# Page_3.net
KiCad netlist of a schematic drawn in Altium Designer
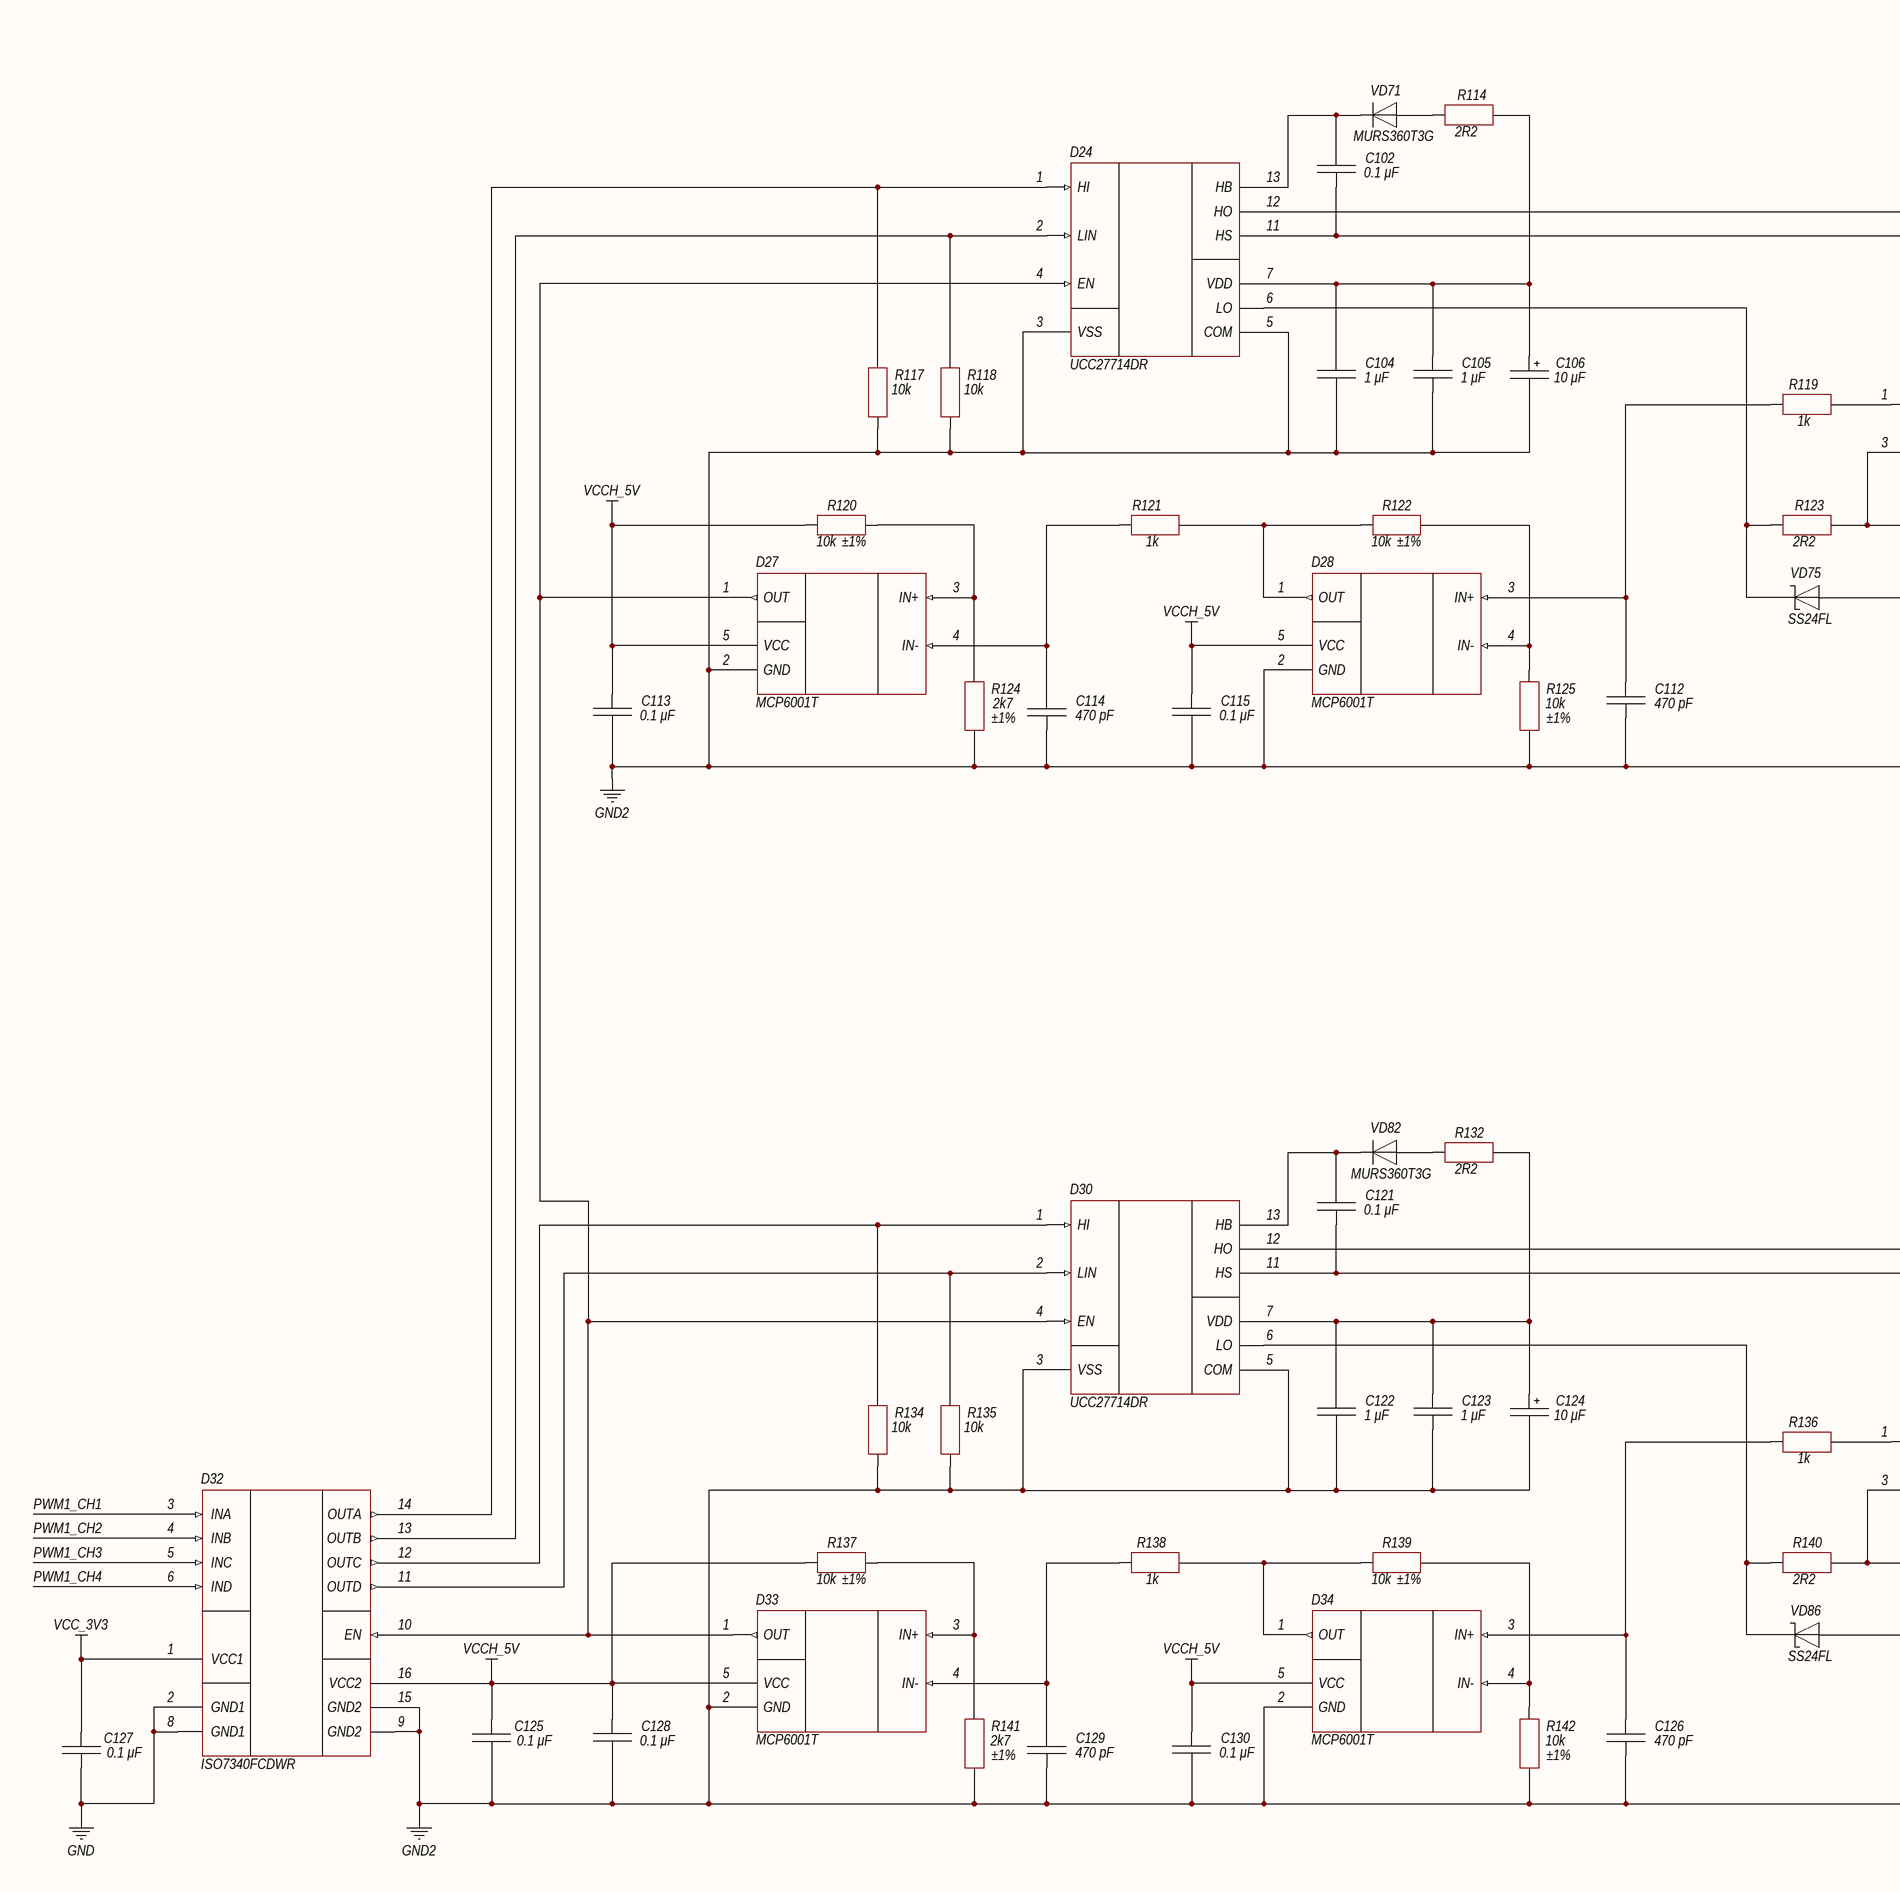
[diagram p0: Page 3.SchDoc, left]
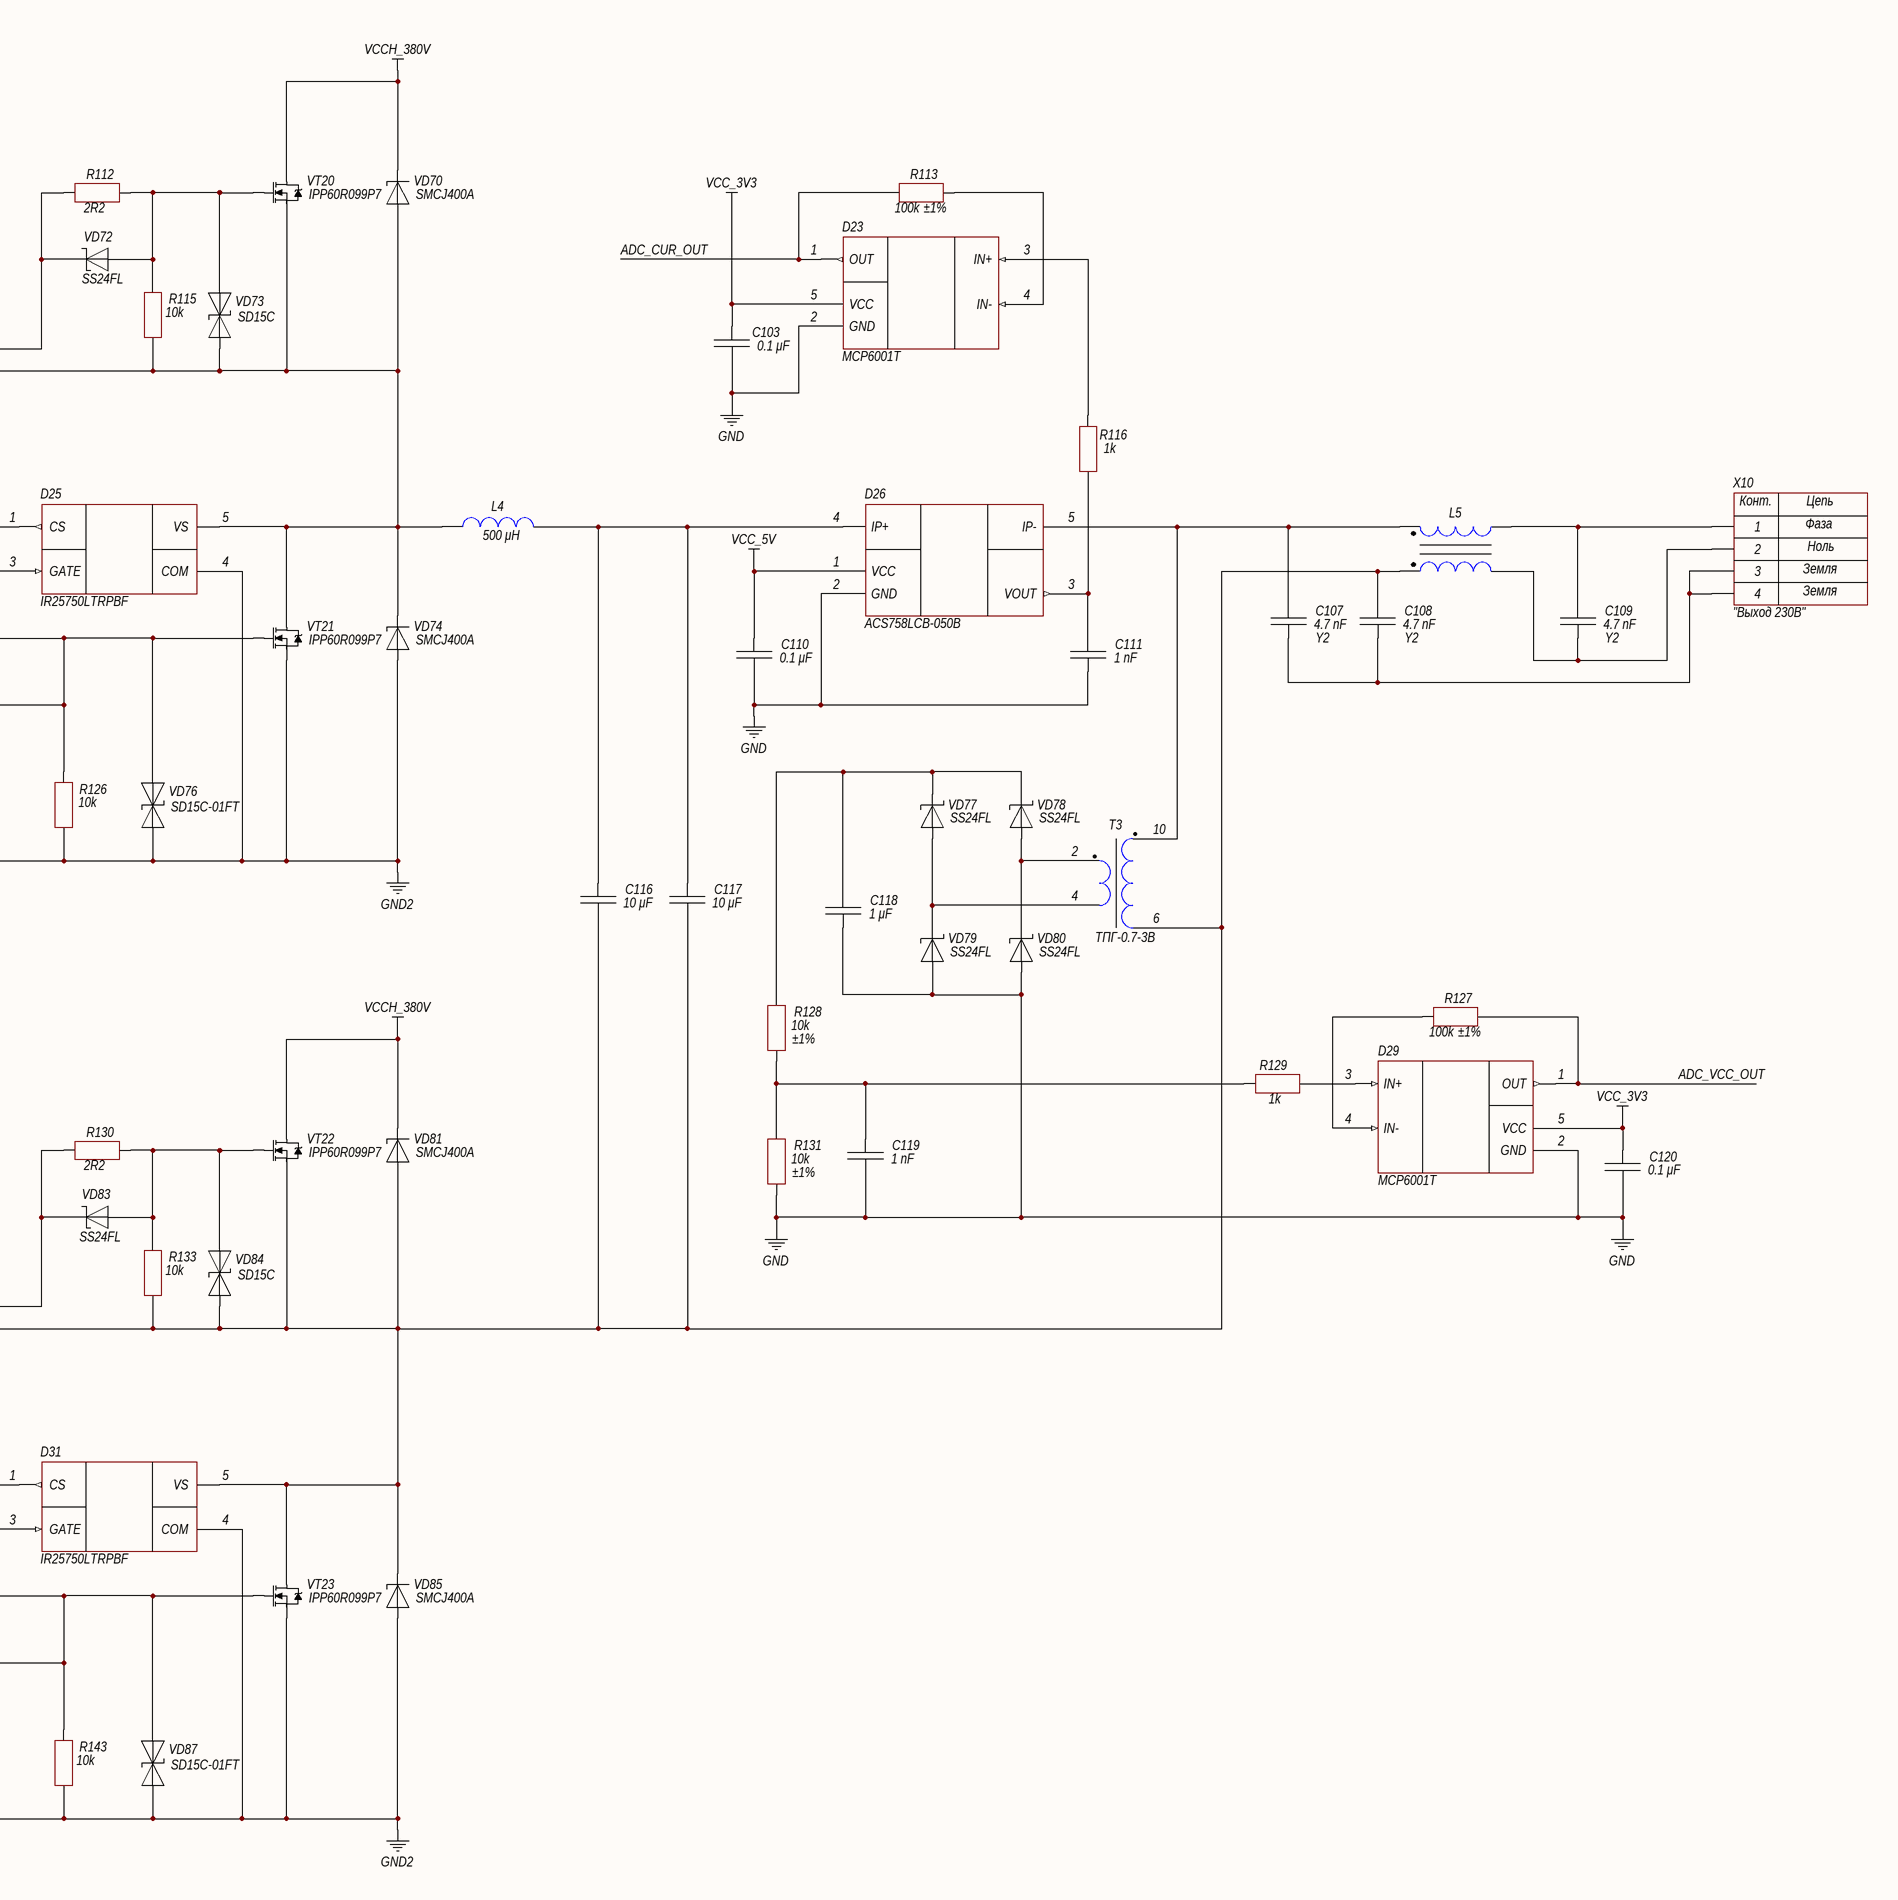
[diagram p1: Page 3.SchDoc, right]

(export (version "E")
  (design (tool "Eeschema 10.0.6"))
  (components
    (comp (ref "C102")
      (value "0.1 μF")
      (footprint "CH0805C")
      (fields (field (name "MANUFACTURER") "Yageo"))
      (libsource (lib "Discrete") (part "Capacitor"))
    )
    (comp (ref "C103")
      (value "0.1 μF")
      (footprint "CH0805C")
      (fields (field (name "MANUFACTURER") "Yageo"))
      (libsource (lib "Discrete") (part "Capacitor"))
    )
    (comp (ref "C104")
      (value "1 μF")
      (footprint "CH0805C")
      (fields (field (name "MANUFACTURER") "Yageo"))
      (libsource (lib "Discrete") (part "Capacitor"))
    )
    (comp (ref "C105")
      (value "1 μF")
      (footprint "CH0805C")
      (fields (field (name "MANUFACTURER") "Yageo"))
      (libsource (lib "Discrete") (part "Capacitor"))
    )
    (comp (ref "C106")
      (value "10 μF")
      (footprint "TANTAL_C")
      (fields (field (name "MANUFACTURER") "Vishay Sprague"))
      (libsource (lib "Discrete") (part "TantalCap"))
    )
    (comp (ref "C107")
      (value "4.7 nF")
      (footprint "CAP: B32021")
      (fields (field (name "MANUFACTURER") "EPCOS (TDK)") (field (name "COMPONENTKIND") "Y2"))
      (libsource (lib "Discrete") (part "Capacitor"))
    )
    (comp (ref "C108")
      (value "4.7 nF")
      (footprint "CAP: B32021")
      (fields (field (name "MANUFACTURER") "EPCOS (TDK)") (field (name "COMPONENTKIND") "Y2"))
      (libsource (lib "Discrete") (part "Capacitor"))
    )
    (comp (ref "C109")
      (value "4.7 nF")
      (footprint "CAP: B32021")
      (fields (field (name "MANUFACTURER") "EPCOS (TDK)") (field (name "COMPONENTKIND") "Y2"))
      (libsource (lib "Discrete") (part "Capacitor"))
    )
    (comp (ref "C110")
      (value "0.1 μF")
      (footprint "CH0805C")
      (fields (field (name "MANUFACTURER") "Yageo"))
      (libsource (lib "Discrete") (part "Capacitor"))
    )
    (comp (ref "C111")
      (value "1 nF")
      (footprint "CH0805C")
      (fields (field (name "MANUFACTURER") "Yageo"))
      (libsource (lib "Discrete") (part "Capacitor"))
    )
    (comp (ref "C112")
      (value "470 pF")
      (footprint "CH0805C")
      (fields (field (name "MANUFACTURER") "Yageo"))
      (libsource (lib "Discrete") (part "Capacitor"))
    )
    (comp (ref "C113")
      (value "0.1 μF")
      (footprint "CH0805C")
      (fields (field (name "MANUFACTURER") "Yageo"))
      (libsource (lib "Discrete") (part "Capacitor"))
    )
    (comp (ref "C114")
      (value "470 pF")
      (footprint "CH0805C")
      (fields (field (name "MANUFACTURER") "Yageo"))
      (libsource (lib "Discrete") (part "Capacitor"))
    )
    (comp (ref "C115")
      (value "0.1 μF")
      (footprint "CH0805C")
      (fields (field (name "MANUFACTURER") "Yageo"))
      (libsource (lib "Discrete") (part "Capacitor"))
    )
    (comp (ref "C116")
      (value "10 μF")
      (footprint "CAP: B32676")
      (fields (field (name "MANUFACTURER") "Epcos"))
      (libsource (lib "Discrete") (part "Capacitor"))
    )
    (comp (ref "C117")
      (value "10 μF")
      (footprint "CAP: B32676")
      (fields (field (name "MANUFACTURER") "Epcos"))
      (libsource (lib "Discrete") (part "Capacitor"))
    )
    (comp (ref "C118")
      (value "1 μF")
      (footprint "CH0805C")
      (fields (field (name "MANUFACTURER") "Yageo"))
      (libsource (lib "Discrete") (part "Capacitor"))
    )
    (comp (ref "C119")
      (value "1 nF")
      (footprint "CH0805C")
      (fields (field (name "MANUFACTURER") "Yageo"))
      (libsource (lib "Discrete") (part "Capacitor"))
    )
    (comp (ref "C120")
      (value "0.1 μF")
      (footprint "CH0805C")
      (fields (field (name "MANUFACTURER") "Yageo"))
      (libsource (lib "Discrete") (part "Capacitor"))
    )
    (comp (ref "C121")
      (value "0.1 μF")
      (footprint "CH0805C")
      (fields (field (name "MANUFACTURER") "Yageo"))
      (libsource (lib "Discrete") (part "Capacitor"))
    )
    (comp (ref "C122")
      (value "1 μF")
      (footprint "CH0805C")
      (fields (field (name "MANUFACTURER") "Yageo"))
      (libsource (lib "Discrete") (part "Capacitor"))
    )
    (comp (ref "C123")
      (value "1 μF")
      (footprint "CH0805C")
      (fields (field (name "MANUFACTURER") "Yageo"))
      (libsource (lib "Discrete") (part "Capacitor"))
    )
    (comp (ref "C124")
      (value "10 μF")
      (footprint "TANTAL_C")
      (fields (field (name "MANUFACTURER") "Vishay Sprague"))
      (libsource (lib "Discrete") (part "TantalCap"))
    )
    (comp (ref "C125")
      (value "0.1 μF")
      (footprint "CH0805C")
      (fields (field (name "MANUFACTURER") "Yageo"))
      (libsource (lib "Discrete") (part "Capacitor"))
    )
    (comp (ref "C126")
      (value "470 pF")
      (footprint "CH0805C")
      (fields (field (name "MANUFACTURER") "Yageo"))
      (libsource (lib "Discrete") (part "Capacitor"))
    )
    (comp (ref "C127")
      (value "0.1 μF")
      (footprint "CH0805C")
      (fields (field (name "MANUFACTURER") "Yageo"))
      (libsource (lib "Discrete") (part "Capacitor"))
    )
    (comp (ref "C128")
      (value "0.1 μF")
      (footprint "CH0805C")
      (fields (field (name "MANUFACTURER") "Yageo"))
      (libsource (lib "Discrete") (part "Capacitor"))
    )
    (comp (ref "C129")
      (value "470 pF")
      (footprint "CH0805C")
      (fields (field (name "MANUFACTURER") "Yageo"))
      (libsource (lib "Discrete") (part "Capacitor"))
    )
    (comp (ref "C130")
      (value "0.1 μF")
      (footprint "CH0805C")
      (fields (field (name "MANUFACTURER") "Yageo"))
      (libsource (lib "Discrete") (part "Capacitor"))
    )
    (comp (ref "D23")
      (value "MCP6001T")
      (footprint "SOT23-5")
      (description "OP amplifier")
      (fields (field (name "MANUFACTURER") "Microchip Technology"))
      (libsource (lib "") (part "MCP6001T_1"))
    )
    (comp (ref "D24")
      (value "UCC27714DR")
      (footprint "14-SOIC")
      (description "Half-bridge driver")
      (fields (field (name "MANUFACTURER") "Texas Instruments"))
      (libsource (lib "Power Supplies") (part "UCC27714DR"))
    )
    (comp (ref "D25")
      (value "IR25750LTRPBF")
      (footprint "SOT23-5")
      (description "Sensor")
      (fields (field (name "MANUFACTURER") "Infineon Technologies"))
      (libsource (lib "Power Supplies") (part "IR25750LTRPBF"))
    )
    (comp (ref "D26")
      (value "ACS758LCB-050B")
      (footprint "IC: ACS770")
      (description "Sensor")
      (fields (field (name "MANUFACTURER") "Allegro MicroSystems, LLC"))
      (libsource (lib "Power Supplies") (part "ACS770LCB"))
    )
    (comp (ref "D27")
      (value "MCP6001T")
      (footprint "SOT23-5")
      (description "OP amplifier")
      (fields (field (name "MANUFACTURER") "Microchip Technology"))
      (libsource (lib "") (part "MCP6001T_1"))
    )
    (comp (ref "D28")
      (value "MCP6001T")
      (footprint "SOT23-5")
      (description "OP amplifier")
      (fields (field (name "MANUFACTURER") "Microchip Technology"))
      (libsource (lib "") (part "MCP6001T_1"))
    )
    (comp (ref "D29")
      (value "MCP6001T")
      (footprint "SOT23-5")
      (description "OP amplifier")
      (fields (field (name "MANUFACTURER") "Microchip Technology"))
      (libsource (lib "Analog") (part "MCP6001T"))
    )
    (comp (ref "D30")
      (value "UCC27714DR")
      (footprint "14-SOIC")
      (description "Half-bridge driver")
      (fields (field (name "MANUFACTURER") "Texas Instruments"))
      (libsource (lib "Power Supplies") (part "UCC27714DR"))
    )
    (comp (ref "D31")
      (value "IR25750LTRPBF")
      (footprint "SOT23-5")
      (description "Sensor")
      (fields (field (name "MANUFACTURER") "Infineon Technologies"))
      (libsource (lib "Power Supplies") (part "IR25750LTRPBF"))
    )
    (comp (ref "D32")
      (value "ISO7340FCDWR")
      (footprint "16-SOIC (W)")
      (description "Isolator")
      (fields (field (name "MANUFACTURER") "Texas Instruments"))
      (libsource (lib "Analog") (part "ISO7340FCDWR"))
    )
    (comp (ref "D33")
      (value "MCP6001T")
      (footprint "SOT23-5")
      (description "OP amplifier")
      (fields (field (name "MANUFACTURER") "Microchip Technology"))
      (libsource (lib "") (part "MCP6001T_1"))
    )
    (comp (ref "D34")
      (value "MCP6001T")
      (footprint "SOT23-5")
      (description "OP amplifier")
      (fields (field (name "MANUFACTURER") "Microchip Technology"))
      (libsource (lib "") (part "MCP6001T_1"))
    )
    (comp (ref "L4")
      (value "500 μH")
      (footprint "IND: R46")
      (fields (field (name "MANUFACTURER") "Magnetics"))
      (libsource (lib "Transformers") (part "Inductor ring"))
    )
    (comp (ref "L5")
      (value "0077071A7")
      (footprint "IND: R32")
      (fields (field (name "MANUFACTURER") "Magnetics"))
      (libsource (lib "Transformers") (part "EMI filter"))
    )
    (comp (ref "R112")
      (value "2R2")
      (footprint "CH0805R")
      (fields (field (name "MANUFACTURER") "Yageo"))
      (libsource (lib "") (part "Resistor_1"))
    )
    (comp (ref "R113")
      (value "100k")
      (footprint "CH0805R")
      (fields (field (name "MANUFACTURER") "Yageo") (field (name "COMPONENTKIND") "±1%"))
      (libsource (lib "") (part "Resistor_3"))
    )
    (comp (ref "R114")
      (value "2R2")
      (footprint "CH0805R")
      (fields (field (name "MANUFACTURER") "Yageo"))
      (libsource (lib "") (part "Resistor_1"))
    )
    (comp (ref "R115")
      (value "10k")
      (footprint "CH0805R")
      (fields (field (name "MANUFACTURER") "Yageo"))
      (libsource (lib "Discrete") (part "Resistor"))
    )
    (comp (ref "R116")
      (value "1k")
      (footprint "CH0805R")
      (fields (field (name "MANUFACTURER") "Yageo"))
      (libsource (lib "") (part "Resistor_1"))
    )
    (comp (ref "R117")
      (value "10k")
      (footprint "CH0805R")
      (fields (field (name "MANUFACTURER") "Yageo"))
      (libsource (lib "Discrete") (part "Resistor"))
    )
    (comp (ref "R118")
      (value "10k")
      (footprint "CH0805R")
      (fields (field (name "MANUFACTURER") "Yageo"))
      (libsource (lib "Discrete") (part "Resistor"))
    )
    (comp (ref "R119")
      (value "1k")
      (footprint "CH0805R")
      (fields (field (name "MANUFACTURER") "Yageo"))
      (libsource (lib "Discrete") (part "Resistor"))
    )
    (comp (ref "R120")
      (value "10k")
      (footprint "CH0805R")
      (fields (field (name "MANUFACTURER") "Yageo") (field (name "COMPONENTKIND") "±1%"))
      (libsource (lib "") (part "Resistor_1"))
    )
    (comp (ref "R121")
      (value "1k")
      (footprint "CH0805R")
      (fields (field (name "MANUFACTURER") "Yageo"))
      (libsource (lib "") (part "Resistor_2"))
    )
    (comp (ref "R122")
      (value "10k")
      (footprint "CH0805R")
      (fields (field (name "MANUFACTURER") "Yageo") (field (name "COMPONENTKIND") "±1%"))
      (libsource (lib "") (part "Resistor_3"))
    )
    (comp (ref "R123")
      (value "2R2")
      (footprint "CH0805R")
      (fields (field (name "MANUFACTURER") "Yageo"))
      (libsource (lib "") (part "Resistor_1"))
    )
    (comp (ref "R124")
      (value "2k7")
      (footprint "CH0805R")
      (fields (field (name "MANUFACTURER") "Yageo") (field (name "COMPONENTKIND") "±1%"))
      (libsource (lib "") (part "Resistor_2"))
    )
    (comp (ref "R125")
      (value "10k")
      (footprint "CH0805R")
      (fields (field (name "MANUFACTURER") "Yageo") (field (name "COMPONENTKIND") "±1%"))
      (libsource (lib "") (part "Resistor_2"))
    )
    (comp (ref "R126")
      (value "10k")
      (footprint "CH0805R")
      (fields (field (name "MANUFACTURER") "Yageo"))
      (libsource (lib "Discrete") (part "Resistor"))
    )
    (comp (ref "R127")
      (value "100k")
      (footprint "CH0805R")
      (fields (field (name "MANUFACTURER") "Yageo") (field (name "COMPONENTKIND") "±1%"))
      (libsource (lib "") (part "Resistor_3"))
    )
    (comp (ref "R128")
      (value "10k")
      (footprint "CH0805R")
      (fields (field (name "MANUFACTURER") "Yageo") (field (name "COMPONENTKIND") "±1%"))
      (libsource (lib "") (part "Resistor_2"))
    )
    (comp (ref "R129")
      (value "1k")
      (footprint "CH0805R")
      (fields (field (name "MANUFACTURER") "Yageo"))
      (libsource (lib "") (part "Resistor_2"))
    )
    (comp (ref "R130")
      (value "2R2")
      (footprint "CH0805R")
      (fields (field (name "MANUFACTURER") "Yageo"))
      (libsource (lib "") (part "Resistor_1"))
    )
    (comp (ref "R131")
      (value "10k")
      (footprint "CH0805R")
      (fields (field (name "MANUFACTURER") "Yageo") (field (name "COMPONENTKIND") "±1%"))
      (libsource (lib "") (part "Resistor_2"))
    )
    (comp (ref "R132")
      (value "2R2")
      (footprint "CH0805R")
      (fields (field (name "MANUFACTURER") "Yageo"))
      (libsource (lib "") (part "Resistor_1"))
    )
    (comp (ref "R133")
      (value "10k")
      (footprint "CH0805R")
      (fields (field (name "MANUFACTURER") "Yageo"))
      (libsource (lib "Discrete") (part "Resistor"))
    )
    (comp (ref "R134")
      (value "10k")
      (footprint "CH0805R")
      (fields (field (name "MANUFACTURER") "Yageo"))
      (libsource (lib "Discrete") (part "Resistor"))
    )
    (comp (ref "R135")
      (value "10k")
      (footprint "CH0805R")
      (fields (field (name "MANUFACTURER") "Yageo"))
      (libsource (lib "Discrete") (part "Resistor"))
    )
    (comp (ref "R136")
      (value "1k")
      (footprint "CH0805R")
      (fields (field (name "MANUFACTURER") "Yageo"))
      (libsource (lib "Discrete") (part "Resistor"))
    )
    (comp (ref "R137")
      (value "10k")
      (footprint "CH0805R")
      (fields (field (name "MANUFACTURER") "Yageo") (field (name "COMPONENTKIND") "±1%"))
      (libsource (lib "") (part "Resistor_1"))
    )
    (comp (ref "R138")
      (value "1k")
      (footprint "CH0805R")
      (fields (field (name "MANUFACTURER") "Yageo"))
      (libsource (lib "") (part "Resistor_2"))
    )
    (comp (ref "R139")
      (value "10k")
      (footprint "CH0805R")
      (fields (field (name "MANUFACTURER") "Yageo") (field (name "COMPONENTKIND") "±1%"))
      (libsource (lib "") (part "Resistor_3"))
    )
    (comp (ref "R140")
      (value "2R2")
      (footprint "CH0805R")
      (fields (field (name "MANUFACTURER") "Yageo"))
      (libsource (lib "") (part "Resistor_1"))
    )
    (comp (ref "R141")
      (value "2k7")
      (footprint "CH0805R")
      (fields (field (name "MANUFACTURER") "Yageo") (field (name "COMPONENTKIND") "±1%"))
      (libsource (lib "") (part "Resistor_2"))
    )
    (comp (ref "R142")
      (value "10k")
      (footprint "CH0805R")
      (fields (field (name "MANUFACTURER") "Yageo") (field (name "COMPONENTKIND") "±1%"))
      (libsource (lib "") (part "Resistor_2"))
    )
    (comp (ref "R143")
      (value "10k")
      (footprint "CH0805R")
      (fields (field (name "MANUFACTURER") "Yageo"))
      (libsource (lib "Discrete") (part "Resistor"))
    )
    (comp (ref "T3")
      (value "ТПГ-0.7-3В")
      (footprint "TRANS: ТПК-7")
      (description "Sensor")
      (fields (field (name "MANUFACTURER") "НПК «Комплекс»"))
      (libsource (lib "Transformers") (part "Sensor"))
    )
    (comp (ref "VD70")
      (value "SMCJ400A")
      (footprint "SMC")
      (fields (field (name "MANUFACTURER") "Littelfuse Inc."))
      (libsource (lib "Diods") (part "Diod Zener"))
    )
    (comp (ref "VD71")
      (value "MURS360T3G")
      (footprint "SMC")
      (fields (field (name "MANUFACTURER") "ON Semiconductor"))
      (libsource (lib "Diods") (part "Diod"))
    )
    (comp (ref "VD72")
      (value "SS24FL")
      (footprint "SOD123F")
      (fields (field (name "MANUFACTURER") "Fairchild/ON Semiconductor"))
      (libsource (lib "Diods") (part "Diod Schottky"))
    )
    (comp (ref "VD73")
      (value "SD15C")
      (footprint "SOD323")
      (fields (field (name "MANUFACTURER") "Littelfuse Inc."))
      (libsource (lib "Diods") (part "TVS-diod"))
    )
    (comp (ref "VD74")
      (value "SMCJ400A")
      (footprint "SMC")
      (fields (field (name "MANUFACTURER") "Littelfuse Inc."))
      (libsource (lib "Diods") (part "Diod Zener"))
    )
    (comp (ref "VD75")
      (value "SS24FL")
      (footprint "SOD123F")
      (fields (field (name "MANUFACTURER") "Fairchild/ON Semiconductor"))
      (libsource (lib "Diods") (part "Diod Schottky"))
    )
    (comp (ref "VD76")
      (value "SD15C-01FT")
      (footprint "SOD323")
      (fields (field (name "MANUFACTURER") "Littelfuse Inc."))
      (libsource (lib "Diods") (part "TVS-diod"))
    )
    (comp (ref "VD77")
      (value "SS24FL")
      (footprint "SOD123F")
      (fields (field (name "MANUFACTURER") "Fairchild/ON Semiconductor"))
      (libsource (lib "Diods") (part "Diod Schottky"))
    )
    (comp (ref "VD78")
      (value "SS24FL")
      (footprint "SOD123F")
      (fields (field (name "MANUFACTURER") "Fairchild/ON Semiconductor"))
      (libsource (lib "Diods") (part "Diod Schottky"))
    )
    (comp (ref "VD79")
      (value "SS24FL")
      (footprint "SOD123F")
      (fields (field (name "MANUFACTURER") "Fairchild/ON Semiconductor"))
      (libsource (lib "Diods") (part "Diod Schottky"))
    )
    (comp (ref "VD80")
      (value "SS24FL")
      (footprint "SOD123F")
      (fields (field (name "MANUFACTURER") "Fairchild/ON Semiconductor"))
      (libsource (lib "Diods") (part "Diod Schottky"))
    )
    (comp (ref "VD81")
      (value "SMCJ400A")
      (footprint "SMC")
      (fields (field (name "MANUFACTURER") "Littelfuse Inc."))
      (libsource (lib "Diods") (part "Diod Zener"))
    )
    (comp (ref "VD82")
      (value "MURS360T3G")
      (footprint "SMC")
      (fields (field (name "MANUFACTURER") "ON Semiconductor"))
      (libsource (lib "Diods") (part "Diod"))
    )
    (comp (ref "VD83")
      (value "SS24FL")
      (footprint "SOD123F")
      (fields (field (name "MANUFACTURER") "Fairchild/ON Semiconductor"))
      (libsource (lib "Diods") (part "Diod Schottky"))
    )
    (comp (ref "VD84")
      (value "SD15C")
      (footprint "SOD323")
      (fields (field (name "MANUFACTURER") "Littelfuse Inc."))
      (libsource (lib "Diods") (part "TVS-diod"))
    )
    (comp (ref "VD85")
      (value "SMCJ400A")
      (footprint "SMC")
      (fields (field (name "MANUFACTURER") "Littelfuse Inc."))
      (libsource (lib "Diods") (part "Diod Zener"))
    )
    (comp (ref "VD86")
      (value "SS24FL")
      (footprint "SOD123F")
      (fields (field (name "MANUFACTURER") "Fairchild/ON Semiconductor"))
      (libsource (lib "Diods") (part "Diod Schottky"))
    )
    (comp (ref "VD87")
      (value "SD15C-01FT")
      (footprint "SOD323")
      (fields (field (name "MANUFACTURER") "Littelfuse Inc."))
      (libsource (lib "Diods") (part "TVS-diod"))
    )
    (comp (ref "VT20")
      (value "IPP60R099P7")
      (footprint "TO220_123")
      (description "Mosfet")
      (fields (field (name "MANUFACTURER") "Infineon Technologies"))
      (libsource (lib "Transistor") (part "N-chanel"))
    )
    (comp (ref "VT21")
      (value "IPP60R099P7")
      (footprint "TO220_123")
      (description "Mosfet")
      (fields (field (name "MANUFACTURER") "Infineon Technologies"))
      (libsource (lib "Transistor") (part "N-chanel"))
    )
    (comp (ref "VT22")
      (value "IPP60R099P7")
      (footprint "TO220_123")
      (description "Mosfet")
      (fields (field (name "MANUFACTURER") "Infineon Technologies"))
      (libsource (lib "Transistor") (part "N-chanel"))
    )
    (comp (ref "VT23")
      (value "IPP60R099P7")
      (footprint "TO220_123")
      (description "Mosfet")
      (fields (field (name "MANUFACTURER") "Infineon Technologies"))
      (libsource (lib "Transistor") (part "N-chanel"))
    )
    (comp (ref "X10")
      (value "\"Выход 230В\"")
      (footprint "CON: X977B04")
      (fields (field (name "MANUFACTURER") "Ningbo Xinya M&E"))
      (libsource (lib "Connectors") (part "4-Connector"))
    )
  )
  (nets
    (net (code "1") (name "/ADC_CUR_OUT") (class "Default")
      (node (ref "D23") (pin "1") (pinfunction "OUT_1") (pintype "output"))
      (node (ref "R113") (pin "1") (pinfunction "1_1") (pintype "passive"))
    )
    (net (code "2") (name "/ADC_VCC_OUT") (class "Default")
      (node (ref "D29") (pin "1") (pinfunction "OUT_1") (pintype "output"))
      (node (ref "R127") (pin "2") (pinfunction "2_2") (pintype "passive"))
    )
    (net (code "3") (name "/PWM1_CH1") (class "Default")
      (node (ref "D32") (pin "3") (pinfunction "INA_3") (pintype "input"))
    )
    (net (code "4") (name "/PWM1_CH2") (class "Default")
      (node (ref "D32") (pin "4") (pinfunction "INB_4") (pintype "input"))
    )
    (net (code "5") (name "/PWM1_CH3") (class "Default")
      (node (ref "D32") (pin "5") (pinfunction "INC_5") (pintype "input"))
    )
    (net (code "6") (name "/PWM1_CH4") (class "Default")
      (node (ref "D32") (pin "6") (pinfunction "IND_6") (pintype "input"))
    )
    (net (code "7") (name "GND") (class "Default")
      (node (ref "C103") (pin "1") (pinfunction "1_1") (pintype "power_in"))
      (node (ref "C110") (pin "1") (pinfunction "1_1") (pintype "power_in"))
      (node (ref "C111") (pin "1") (pinfunction "1_1") (pintype "power_in"))
      (node (ref "C118") (pin "1") (pinfunction "1_1") (pintype "power_in"))
      (node (ref "C119") (pin "1") (pinfunction "1_1") (pintype "power_in"))
      (node (ref "C120") (pin "1") (pinfunction "1_1") (pintype "power_in"))
      (node (ref "C127") (pin "1") (pinfunction "1_1") (pintype "power_in"))
      (node (ref "D23") (pin "2") (pinfunction "GND_2") (pintype "power_in"))
      (node (ref "D26") (pin "2") (pinfunction "GND_2") (pintype "passive"))
      (node (ref "D29") (pin "2") (pinfunction "GND_2") (pintype "power_in"))
      (node (ref "D32") (pin "2") (pinfunction "GND1_2") (pintype "power_in"))
      (node (ref "D32") (pin "8") (pinfunction "GND1_8") (pintype "power_in"))
      (node (ref "R131") (pin "2") (pinfunction "2_2") (pintype "passive"))
      (node (ref "VD79") (pin "1") (pinfunction "1_1") (pintype "passive"))
      (node (ref "VD80") (pin "1") (pinfunction "1_1") (pintype "passive"))
    )
    (net (code "8") (name "GND2") (class "Default")
      (node (ref "C104") (pin "1") (pinfunction "1_1") (pintype "power_in"))
      (node (ref "C105") (pin "1") (pinfunction "1_1") (pintype "power_in"))
      (node (ref "C106") (pin "2") (pinfunction "2_2") (pintype "power_in"))
      (node (ref "C112") (pin "2") (pinfunction "2_2") (pintype "power_in"))
      (node (ref "C113") (pin "1") (pinfunction "1_1") (pintype "power_in"))
      (node (ref "C114") (pin "2") (pinfunction "2_2") (pintype "power_in"))
      (node (ref "C115") (pin "1") (pinfunction "1_1") (pintype "power_in"))
      (node (ref "C122") (pin "1") (pinfunction "1_1") (pintype "power_in"))
      (node (ref "C123") (pin "1") (pinfunction "1_1") (pintype "power_in"))
      (node (ref "C124") (pin "2") (pinfunction "2_2") (pintype "power_in"))
      (node (ref "C125") (pin "1") (pinfunction "1_1") (pintype "power_in"))
      (node (ref "C126") (pin "2") (pinfunction "2_2") (pintype "power_in"))
      (node (ref "C128") (pin "1") (pinfunction "1_1") (pintype "power_in"))
      (node (ref "C129") (pin "2") (pinfunction "2_2") (pintype "power_in"))
      (node (ref "C130") (pin "1") (pinfunction "1_1") (pintype "power_in"))
      (node (ref "D24") (pin "3") (pinfunction "VSS_3") (pintype "passive"))
      (node (ref "D24") (pin "5") (pinfunction "COM_5") (pintype "passive"))
      (node (ref "D25") (pin "4") (pinfunction "COM_4") (pintype "power_in"))
      (node (ref "D27") (pin "2") (pinfunction "GND_2") (pintype "power_in"))
      (node (ref "D28") (pin "2") (pinfunction "GND_2") (pintype "power_in"))
      (node (ref "D30") (pin "3") (pinfunction "VSS_3") (pintype "passive"))
      (node (ref "D30") (pin "5") (pinfunction "COM_5") (pintype "passive"))
      (node (ref "D31") (pin "4") (pinfunction "COM_4") (pintype "power_in"))
      (node (ref "D32") (pin "15") (pinfunction "GND2_15") (pintype "power_in"))
      (node (ref "D32") (pin "9") (pinfunction "GND2_9") (pintype "power_in"))
      (node (ref "D33") (pin "2") (pinfunction "GND_2") (pintype "power_in"))
      (node (ref "D34") (pin "2") (pinfunction "GND_2") (pintype "power_in"))
      (node (ref "R117") (pin "1") (pinfunction "1_1") (pintype "passive"))
      (node (ref "R118") (pin "1") (pinfunction "1_1") (pintype "passive"))
      (node (ref "R124") (pin "2") (pinfunction "2_2") (pintype "passive"))
      (node (ref "R125") (pin "2") (pinfunction "2_2") (pintype "passive"))
      (node (ref "R126") (pin "1") (pinfunction "1_1") (pintype "passive"))
      (node (ref "R134") (pin "1") (pinfunction "1_1") (pintype "passive"))
      (node (ref "R135") (pin "1") (pinfunction "1_1") (pintype "passive"))
      (node (ref "R141") (pin "2") (pinfunction "2_2") (pintype "passive"))
      (node (ref "R142") (pin "2") (pinfunction "2_2") (pintype "passive"))
      (node (ref "R143") (pin "1") (pinfunction "1_1") (pintype "passive"))
      (node (ref "VD74") (pin "1") (pinfunction "A_1") (pintype "passive"))
      (node (ref "VD76") (pin "1") (pinfunction "A_1") (pintype "passive"))
      (node (ref "VD85") (pin "1") (pinfunction "A_1") (pintype "passive"))
      (node (ref "VD87") (pin "1") (pinfunction "A_1") (pintype "passive"))
      (node (ref "VT21") (pin "3") (pinfunction "S_3") (pintype "passive"))
      (node (ref "VT23") (pin "3") (pinfunction "S_3") (pintype "passive"))
    )
    (net (code "9") (name "Net-(C107-Pad1)") (class "Default")
      (node (ref "C107") (pin "1") (pinfunction "1_1") (pintype "power_in"))
      (node (ref "C108") (pin "1") (pinfunction "1_1") (pintype "power_in"))
      (node (ref "X10") (pin "3") (pinfunction "3_3") (pintype "power_in"))
      (node (ref "X10") (pin "4") (pinfunction "4_4") (pintype "power_in"))
    )
    (net (code "10") (name "Net-(C109-Pad1)") (class "Default")
      (node (ref "C109") (pin "1") (pinfunction "1_1") (pintype "power_in"))
      (node (ref "L5") (pin "4") (pinfunction "4_4") (pintype "passive"))
      (node (ref "X10") (pin "2") (pinfunction "2_2") (pintype "passive"))
    )
    (net (code "11") (name "Net-(C109-Pad2)") (class "Default")
      (node (ref "C109") (pin "2") (pinfunction "2_2") (pintype "power_in"))
      (node (ref "L5") (pin "2") (pinfunction "2_2") (pintype "passive"))
      (node (ref "X10") (pin "1") (pinfunction "1_1") (pintype "passive"))
    )
    (net (code "12") (name "Net-(C118-Pad2)") (class "Default")
      (node (ref "C118") (pin "2") (pinfunction "2_2") (pintype "power_in"))
      (node (ref "R128") (pin "1") (pinfunction "1_1") (pintype "passive"))
      (node (ref "VD77") (pin "2") (pinfunction "2_2") (pintype "passive"))
      (node (ref "VD78") (pin "2") (pinfunction "2_2") (pintype "passive"))
    )
    (net (code "13") (name "Net-(C119-Pad2)") (class "Default")
      (node (ref "C119") (pin "2") (pinfunction "2_2") (pintype "power_in"))
      (node (ref "R128") (pin "2") (pinfunction "2_2") (pintype "passive"))
      (node (ref "R129") (pin "2") (pinfunction "2_2") (pintype "passive"))
      (node (ref "R131") (pin "1") (pinfunction "1_1") (pintype "passive"))
    )
    (net (code "14") (name "Net-(D23-IN+)") (class "Default")
      (node (ref "D23") (pin "3") (pinfunction "IN+_3") (pintype "input"))
      (node (ref "R116") (pin "1") (pinfunction "1_1") (pintype "passive"))
    )
    (net (code "15") (name "Net-(D23-IN-)") (class "Default")
      (node (ref "D23") (pin "4") (pinfunction "IN-_4") (pintype "input"))
      (node (ref "R113") (pin "2") (pinfunction "2_2") (pintype "passive"))
    )
    (net (code "16") (name "Net-(D24-EN)") (class "Default")
      (node (ref "D24") (pin "4") (pinfunction "EN_4") (pintype "input"))
      (node (ref "D27") (pin "1") (pinfunction "OUT_1") (pintype "output"))
      (node (ref "D30") (pin "4") (pinfunction "EN_4") (pintype "input"))
      (node (ref "D32") (pin "10") (pinfunction "EN_10") (pintype "input"))
      (node (ref "D33") (pin "1") (pinfunction "OUT_1") (pintype "output"))
    )
    (net (code "17") (name "Net-(D24-HB)") (class "Default")
      (node (ref "C102") (pin "2") (pinfunction "2_2") (pintype "power_in"))
      (node (ref "D24") (pin "13") (pinfunction "HB_13") (pintype "passive"))
      (node (ref "VD71") (pin "2") (pinfunction "2_2") (pintype "passive"))
    )
    (net (code "18") (name "Net-(D24-HI)") (class "Default")
      (node (ref "D24") (pin "1") (pinfunction "HI_1") (pintype "input"))
      (node (ref "D32") (pin "14") (pinfunction "OUTA_14") (pintype "output"))
      (node (ref "R117") (pin "2") (pinfunction "2_2") (pintype "passive"))
    )
    (net (code "19") (name "Net-(D24-HO)") (class "Default")
      (node (ref "D24") (pin "12") (pinfunction "HO_12") (pintype "passive"))
      (node (ref "R112") (pin "2") (pinfunction "2_2") (pintype "passive"))
      (node (ref "VD72") (pin "2") (pinfunction "2_2") (pintype "passive"))
    )
    (net (code "20") (name "Net-(D24-HS)") (class "Default")
      (node (ref "C102") (pin "1") (pinfunction "1_1") (pintype "power_in"))
      (node (ref "D24") (pin "11") (pinfunction "HS_11") (pintype "passive"))
      (node (ref "D25") (pin "5") (pinfunction "VS_5") (pintype "power_in"))
      (node (ref "L4") (pin "2") (pinfunction "2_2") (pintype "passive"))
      (node (ref "R115") (pin "1") (pinfunction "1_1") (pintype "passive"))
      (node (ref "VD70") (pin "1") (pinfunction "A_1") (pintype "passive"))
      (node (ref "VD73") (pin "1") (pinfunction "A_1") (pintype "passive"))
      (node (ref "VD74") (pin "2") (pinfunction "C_2") (pintype "passive"))
      (node (ref "VT20") (pin "3") (pinfunction "S_3") (pintype "passive"))
      (node (ref "VT21") (pin "2") (pinfunction "D_2") (pintype "passive"))
    )
    (net (code "21") (name "Net-(D24-LIN)") (class "Default")
      (node (ref "D24") (pin "2") (pinfunction "LIN_2") (pintype "input"))
      (node (ref "D32") (pin "13") (pinfunction "OUTB_13") (pintype "output"))
      (node (ref "R118") (pin "2") (pinfunction "2_2") (pintype "passive"))
    )
    (net (code "22") (name "Net-(D24-LO)") (class "Default")
      (node (ref "D24") (pin "6") (pinfunction "LO_6") (pintype "passive"))
      (node (ref "R123") (pin "2") (pinfunction "2_2") (pintype "passive"))
      (node (ref "VD75") (pin "2") (pinfunction "2_2") (pintype "passive"))
    )
    (net (code "23") (name "Net-(D24-VDD)") (class "Default")
      (node (ref "C104") (pin "2") (pinfunction "2_2") (pintype "power_in"))
      (node (ref "C105") (pin "2") (pinfunction "2_2") (pintype "power_in"))
      (node (ref "C106") (pin "1") (pinfunction "1_1") (pintype "power_in"))
      (node (ref "D24") (pin "7") (pinfunction "VDD_7") (pintype "passive"))
      (node (ref "R114") (pin "1") (pinfunction "1_1") (pintype "passive"))
    )
    (net (code "24") (name "Net-(D25-CS)") (class "Default")
      (node (ref "D25") (pin "1") (pinfunction "CS_1") (pintype "output"))
      (node (ref "R119") (pin "2") (pinfunction "2_2") (pintype "passive"))
    )
    (net (code "25") (name "Net-(D25-GATE)") (class "Default")
      (node (ref "D25") (pin "3") (pinfunction "GATE_3") (pintype "input"))
      (node (ref "R123") (pin "1") (pinfunction "1_1") (pintype "passive"))
      (node (ref "R126") (pin "2") (pinfunction "2_2") (pintype "passive"))
      (node (ref "VD75") (pin "1") (pinfunction "1_1") (pintype "passive"))
      (node (ref "VD76") (pin "2") (pinfunction "C_2") (pintype "passive"))
      (node (ref "VT21") (pin "1") (pinfunction "G_1") (pintype "passive"))
    )
    (net (code "26") (name "Net-(D26-IP+)") (class "Default")
      (node (ref "C116") (pin "2") (pinfunction "2_2") (pintype "power_in"))
      (node (ref "C117") (pin "2") (pinfunction "2_2") (pintype "power_in"))
      (node (ref "D26") (pin "4") (pinfunction "IP+_4") (pintype "passive"))
      (node (ref "L4") (pin "1") (pinfunction "1_1") (pintype "passive"))
    )
    (net (code "27") (name "Net-(D26-IP-)") (class "Default")
      (node (ref "C107") (pin "2") (pinfunction "2_2") (pintype "power_in"))
      (node (ref "D26") (pin "5") (pinfunction "IP-_5") (pintype "passive"))
      (node (ref "L5") (pin "1") (pinfunction "1_1") (pintype "passive"))
      (node (ref "T3") (pin "10") (pinfunction "10_10") (pintype "power_in"))
    )
    (net (code "28") (name "Net-(D26-VOUT)") (class "Default")
      (node (ref "C111") (pin "2") (pinfunction "2_2") (pintype "power_in"))
      (node (ref "D26") (pin "3") (pinfunction "VOUT_3") (pintype "output"))
      (node (ref "R116") (pin "2") (pinfunction "2_2") (pintype "passive"))
    )
    (net (code "29") (name "Net-(D27-IN+)") (class "Default")
      (node (ref "D27") (pin "3") (pinfunction "IN+_3") (pintype "input"))
      (node (ref "R120") (pin "1") (pinfunction "1_1") (pintype "passive"))
      (node (ref "R124") (pin "1") (pinfunction "1_1") (pintype "passive"))
    )
    (net (code "30") (name "Net-(D27-IN-)") (class "Default")
      (node (ref "C114") (pin "1") (pinfunction "1_1") (pintype "power_in"))
      (node (ref "D27") (pin "4") (pinfunction "IN-_4") (pintype "input"))
      (node (ref "R121") (pin "2") (pinfunction "2_2") (pintype "passive"))
    )
    (net (code "31") (name "Net-(D28-IN+)") (class "Default")
      (node (ref "C112") (pin "1") (pinfunction "1_1") (pintype "power_in"))
      (node (ref "D28") (pin "3") (pinfunction "IN+_3") (pintype "input"))
      (node (ref "R119") (pin "1") (pinfunction "1_1") (pintype "passive"))
    )
    (net (code "32") (name "Net-(D28-IN-)") (class "Default")
      (node (ref "D28") (pin "4") (pinfunction "IN-_4") (pintype "input"))
      (node (ref "R122") (pin "2") (pinfunction "2_2") (pintype "passive"))
      (node (ref "R125") (pin "1") (pinfunction "1_1") (pintype "passive"))
    )
    (net (code "33") (name "Net-(D28-OUT)") (class "Default")
      (node (ref "D28") (pin "1") (pinfunction "OUT_1") (pintype "output"))
      (node (ref "R121") (pin "1") (pinfunction "1_1") (pintype "passive"))
      (node (ref "R122") (pin "1") (pinfunction "1_1") (pintype "passive"))
    )
    (net (code "34") (name "Net-(D29-IN+)") (class "Default")
      (node (ref "D29") (pin "3") (pinfunction "IN+_3") (pintype "input"))
      (node (ref "R129") (pin "1") (pinfunction "1_1") (pintype "passive"))
    )
    (net (code "35") (name "Net-(D29-IN-)") (class "Default")
      (node (ref "D29") (pin "4") (pinfunction "IN-_4") (pintype "input"))
      (node (ref "R127") (pin "1") (pinfunction "1_1") (pintype "passive"))
    )
    (net (code "36") (name "Net-(D30-HB)") (class "Default")
      (node (ref "C121") (pin "2") (pinfunction "2_2") (pintype "power_in"))
      (node (ref "D30") (pin "13") (pinfunction "HB_13") (pintype "passive"))
      (node (ref "VD82") (pin "2") (pinfunction "2_2") (pintype "passive"))
    )
    (net (code "37") (name "Net-(D30-HI)") (class "Default")
      (node (ref "D30") (pin "1") (pinfunction "HI_1") (pintype "input"))
      (node (ref "D32") (pin "12") (pinfunction "OUTC_12") (pintype "output"))
      (node (ref "R134") (pin "2") (pinfunction "2_2") (pintype "passive"))
    )
    (net (code "38") (name "Net-(D30-HO)") (class "Default")
      (node (ref "D30") (pin "12") (pinfunction "HO_12") (pintype "passive"))
      (node (ref "R130") (pin "2") (pinfunction "2_2") (pintype "passive"))
      (node (ref "VD83") (pin "2") (pinfunction "2_2") (pintype "passive"))
    )
    (net (code "39") (name "Net-(D30-HS)") (class "Default")
      (node (ref "C108") (pin "2") (pinfunction "2_2") (pintype "power_in"))
      (node (ref "C116") (pin "1") (pinfunction "1_1") (pintype "power_in"))
      (node (ref "C117") (pin "1") (pinfunction "1_1") (pintype "power_in"))
      (node (ref "C121") (pin "1") (pinfunction "1_1") (pintype "power_in"))
      (node (ref "D30") (pin "11") (pinfunction "HS_11") (pintype "passive"))
      (node (ref "D31") (pin "5") (pinfunction "VS_5") (pintype "power_in"))
      (node (ref "L5") (pin "3") (pinfunction "3_3") (pintype "passive"))
      (node (ref "R133") (pin "1") (pinfunction "1_1") (pintype "passive"))
      (node (ref "T3") (pin "6") (pinfunction "6_6") (pintype "power_in"))
      (node (ref "VD81") (pin "1") (pinfunction "A_1") (pintype "passive"))
      (node (ref "VD84") (pin "1") (pinfunction "A_1") (pintype "passive"))
      (node (ref "VD85") (pin "2") (pinfunction "C_2") (pintype "passive"))
      (node (ref "VT22") (pin "3") (pinfunction "S_3") (pintype "passive"))
      (node (ref "VT23") (pin "2") (pinfunction "D_2") (pintype "passive"))
    )
    (net (code "40") (name "Net-(D30-LIN)") (class "Default")
      (node (ref "D30") (pin "2") (pinfunction "LIN_2") (pintype "input"))
      (node (ref "D32") (pin "11") (pinfunction "OUTD_11") (pintype "output"))
      (node (ref "R135") (pin "2") (pinfunction "2_2") (pintype "passive"))
    )
    (net (code "41") (name "Net-(D30-LO)") (class "Default")
      (node (ref "D30") (pin "6") (pinfunction "LO_6") (pintype "passive"))
      (node (ref "R140") (pin "2") (pinfunction "2_2") (pintype "passive"))
      (node (ref "VD86") (pin "2") (pinfunction "2_2") (pintype "passive"))
    )
    (net (code "42") (name "Net-(D30-VDD)") (class "Default")
      (node (ref "C122") (pin "2") (pinfunction "2_2") (pintype "power_in"))
      (node (ref "C123") (pin "2") (pinfunction "2_2") (pintype "power_in"))
      (node (ref "C124") (pin "1") (pinfunction "1_1") (pintype "power_in"))
      (node (ref "D30") (pin "7") (pinfunction "VDD_7") (pintype "passive"))
      (node (ref "R132") (pin "1") (pinfunction "1_1") (pintype "passive"))
    )
    (net (code "43") (name "Net-(D31-CS)") (class "Default")
      (node (ref "D31") (pin "1") (pinfunction "CS_1") (pintype "output"))
      (node (ref "R136") (pin "2") (pinfunction "2_2") (pintype "passive"))
    )
    (net (code "44") (name "Net-(D31-GATE)") (class "Default")
      (node (ref "D31") (pin "3") (pinfunction "GATE_3") (pintype "input"))
      (node (ref "R140") (pin "1") (pinfunction "1_1") (pintype "passive"))
      (node (ref "R143") (pin "2") (pinfunction "2_2") (pintype "passive"))
      (node (ref "VD86") (pin "1") (pinfunction "1_1") (pintype "passive"))
      (node (ref "VD87") (pin "2") (pinfunction "C_2") (pintype "passive"))
      (node (ref "VT23") (pin "1") (pinfunction "G_1") (pintype "passive"))
    )
    (net (code "45") (name "Net-(D33-IN+)") (class "Default")
      (node (ref "D33") (pin "3") (pinfunction "IN+_3") (pintype "input"))
      (node (ref "R137") (pin "1") (pinfunction "1_1") (pintype "passive"))
      (node (ref "R141") (pin "1") (pinfunction "1_1") (pintype "passive"))
    )
    (net (code "46") (name "Net-(D33-IN-)") (class "Default")
      (node (ref "C129") (pin "1") (pinfunction "1_1") (pintype "power_in"))
      (node (ref "D33") (pin "4") (pinfunction "IN-_4") (pintype "input"))
      (node (ref "R138") (pin "2") (pinfunction "2_2") (pintype "passive"))
    )
    (net (code "47") (name "Net-(D34-IN+)") (class "Default")
      (node (ref "C126") (pin "1") (pinfunction "1_1") (pintype "power_in"))
      (node (ref "D34") (pin "3") (pinfunction "IN+_3") (pintype "input"))
      (node (ref "R136") (pin "1") (pinfunction "1_1") (pintype "passive"))
    )
    (net (code "48") (name "Net-(D34-IN-)") (class "Default")
      (node (ref "D34") (pin "4") (pinfunction "IN-_4") (pintype "input"))
      (node (ref "R139") (pin "2") (pinfunction "2_2") (pintype "passive"))
      (node (ref "R142") (pin "1") (pinfunction "1_1") (pintype "passive"))
    )
    (net (code "49") (name "Net-(D34-OUT)") (class "Default")
      (node (ref "D34") (pin "1") (pinfunction "OUT_1") (pintype "output"))
      (node (ref "R138") (pin "1") (pinfunction "1_1") (pintype "passive"))
      (node (ref "R139") (pin "1") (pinfunction "1_1") (pintype "passive"))
    )
    (net (code "50") (name "Net-(R114-Pad2)") (class "Default")
      (node (ref "R114") (pin "2") (pinfunction "2_2") (pintype "passive"))
      (node (ref "VD71") (pin "1") (pinfunction "1_1") (pintype "passive"))
    )
    (net (code "51") (name "Net-(R132-Pad2)") (class "Default")
      (node (ref "R132") (pin "2") (pinfunction "2_2") (pintype "passive"))
      (node (ref "VD82") (pin "1") (pinfunction "1_1") (pintype "passive"))
    )
    (net (code "52") (name "Net-(T3-Pad2)") (class "Default")
      (node (ref "T3") (pin "2") (pinfunction "2_2") (pintype "power_in"))
      (node (ref "VD78") (pin "1") (pinfunction "1_1") (pintype "passive"))
      (node (ref "VD80") (pin "2") (pinfunction "2_2") (pintype "passive"))
    )
    (net (code "53") (name "Net-(T3-Pad4)") (class "Default")
      (node (ref "T3") (pin "4") (pinfunction "4_4") (pintype "power_in"))
      (node (ref "VD77") (pin "1") (pinfunction "1_1") (pintype "passive"))
      (node (ref "VD79") (pin "2") (pinfunction "2_2") (pintype "passive"))
    )
    (net (code "54") (name "Net-(VD73-C)") (class "Default")
      (node (ref "R112") (pin "1") (pinfunction "1_1") (pintype "passive"))
      (node (ref "R115") (pin "2") (pinfunction "2_2") (pintype "passive"))
      (node (ref "VD72") (pin "1") (pinfunction "1_1") (pintype "passive"))
      (node (ref "VD73") (pin "2") (pinfunction "C_2") (pintype "passive"))
      (node (ref "VT20") (pin "1") (pinfunction "G_1") (pintype "passive"))
    )
    (net (code "55") (name "Net-(VD84-C)") (class "Default")
      (node (ref "R130") (pin "1") (pinfunction "1_1") (pintype "passive"))
      (node (ref "R133") (pin "2") (pinfunction "2_2") (pintype "passive"))
      (node (ref "VD83") (pin "1") (pinfunction "1_1") (pintype "passive"))
      (node (ref "VD84") (pin "2") (pinfunction "C_2") (pintype "passive"))
      (node (ref "VT22") (pin "1") (pinfunction "G_1") (pintype "passive"))
    )
    (net (code "56") (name "VCCH_5V") (class "Default")
      (node (ref "C113") (pin "2") (pinfunction "2_2") (pintype "power_in"))
      (node (ref "C115") (pin "2") (pinfunction "2_2") (pintype "power_in"))
      (node (ref "C125") (pin "2") (pinfunction "2_2") (pintype "power_in"))
      (node (ref "C128") (pin "2") (pinfunction "2_2") (pintype "power_in"))
      (node (ref "C130") (pin "2") (pinfunction "2_2") (pintype "power_in"))
      (node (ref "D27") (pin "5") (pinfunction "VCC_5") (pintype "power_in"))
      (node (ref "D28") (pin "5") (pinfunction "VCC_5") (pintype "power_in"))
      (node (ref "D32") (pin "16") (pinfunction "VCC2_16") (pintype "power_in"))
      (node (ref "D33") (pin "5") (pinfunction "VCC_5") (pintype "power_in"))
      (node (ref "D34") (pin "5") (pinfunction "VCC_5") (pintype "power_in"))
      (node (ref "R120") (pin "2") (pinfunction "2_2") (pintype "passive"))
      (node (ref "R137") (pin "2") (pinfunction "2_2") (pintype "passive"))
    )
    (net (code "57") (name "VCCH_380V") (class "Default")
      (node (ref "VD70") (pin "2") (pinfunction "C_2") (pintype "passive"))
      (node (ref "VD81") (pin "2") (pinfunction "C_2") (pintype "passive"))
      (node (ref "VT20") (pin "2") (pinfunction "D_2") (pintype "passive"))
      (node (ref "VT22") (pin "2") (pinfunction "D_2") (pintype "passive"))
    )
    (net (code "58") (name "VCC_3V3") (class "Default")
      (node (ref "C103") (pin "2") (pinfunction "2_2") (pintype "power_in"))
      (node (ref "C120") (pin "2") (pinfunction "2_2") (pintype "power_in"))
      (node (ref "C127") (pin "2") (pinfunction "2_2") (pintype "power_in"))
      (node (ref "D23") (pin "5") (pinfunction "VCC_5") (pintype "power_in"))
      (node (ref "D29") (pin "5") (pinfunction "VCC_5") (pintype "power_in"))
      (node (ref "D32") (pin "1") (pinfunction "VCC1_1") (pintype "power_in"))
    )
    (net (code "59") (name "VCC_5V") (class "Default")
      (node (ref "C110") (pin "2") (pinfunction "2_2") (pintype "power_in"))
      (node (ref "D26") (pin "1") (pinfunction "VCC_1") (pintype "passive"))
    )
  )
)
